# USBStereoAudioCodec.net
KiCad netlist of a schematic drawn in Altium Designer
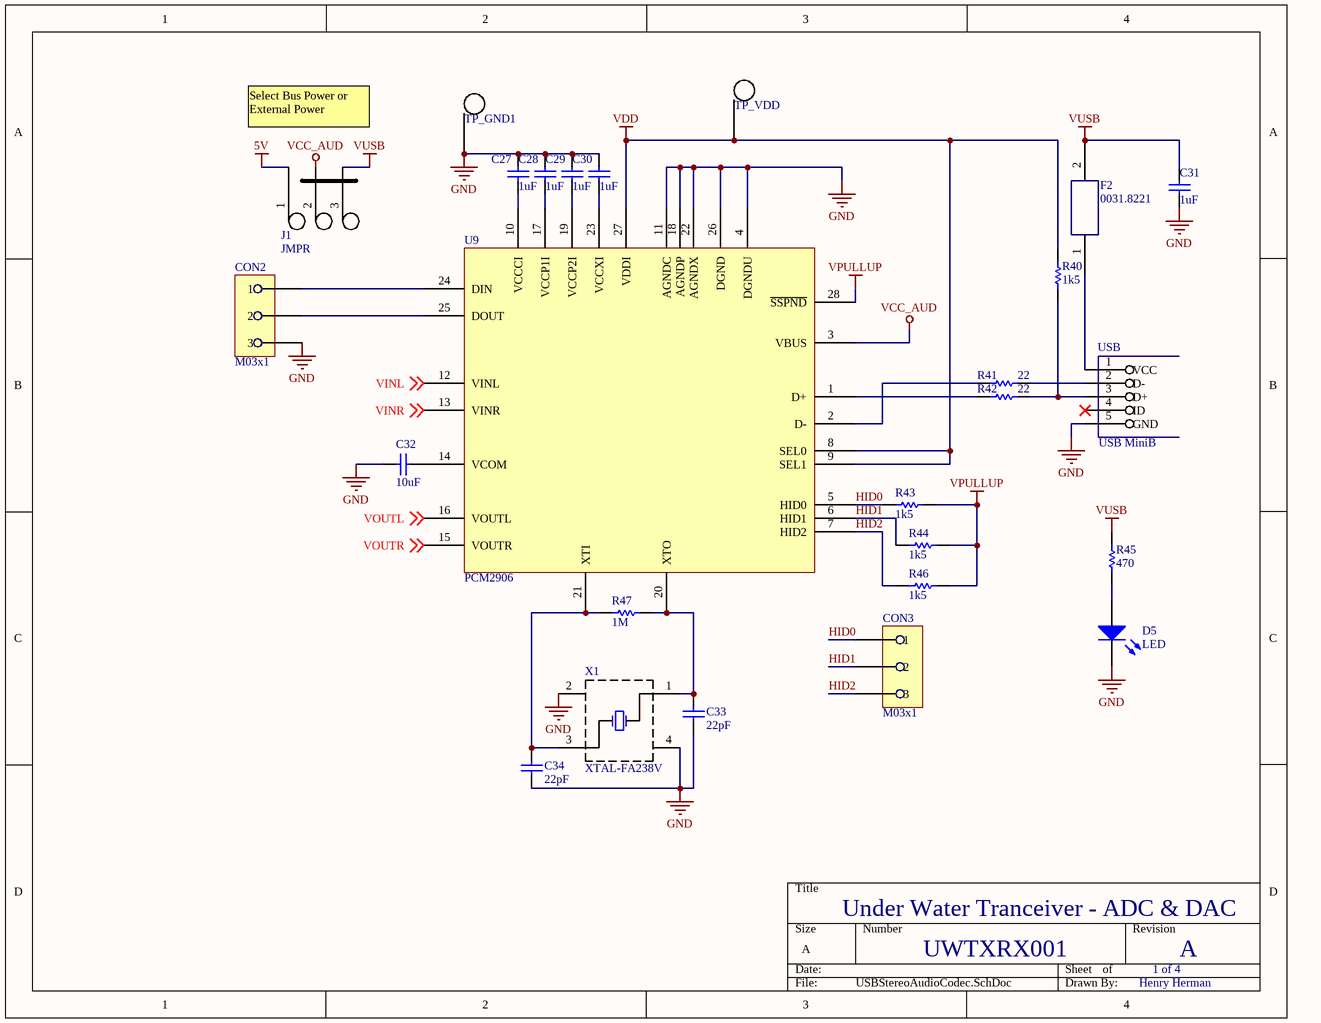
[diagram p0: USBStereoAudioCodec.SchDoc]

(export (version "E")
  (design (tool "Eeschema 10.0.6"))
  (components
    (comp (ref "C27")
      (value "1uF")
      (footprint "SM/C_0805")
      (description "CAP")
      (libsource (lib "Henry1_20_2010") (part "CAP"))
    )
    (comp (ref "C28")
      (value "1uF")
      (footprint "SM/C_0805")
      (description "CAP")
      (libsource (lib "Henry1_20_2010") (part "CAP"))
    )
    (comp (ref "C29")
      (value "1uF")
      (footprint "SM/C_0805")
      (description "CAP")
      (libsource (lib "Henry1_20_2010") (part "CAP"))
    )
    (comp (ref "C30")
      (value "1uF")
      (footprint "SM/C_0805")
      (description "CAP")
      (libsource (lib "Henry1_20_2010") (part "CAP"))
    )
    (comp (ref "C31")
      (value "1uF")
      (footprint "SM/C_0805")
      (description "CAP")
      (libsource (lib "Henry1_20_2010") (part "CAP"))
    )
    (comp (ref "C32")
      (value "10uF")
      (footprint "SM/C_0805")
      (description "CAP")
      (libsource (lib "Henry1_20_2010") (part "CAP"))
    )
    (comp (ref "C33")
      (value "22pF")
      (footprint "SM/C_0805")
      (description "CAP")
      (libsource (lib "Henry1_20_2010") (part "CAP"))
    )
    (comp (ref "C34")
      (value "22pF")
      (footprint "SM/C_0805")
      (description "CAP")
      (libsource (lib "Henry1_20_2010") (part "CAP"))
    )
    (comp (ref "CON2") (value "M03x1") (footprint "M03x1") (libsource (lib "") (part "M03x1_1")))
    (comp (ref "CON3") (value "M03x1") (footprint "M03x1") (libsource (lib "Henry1_20_2010") (part "M03x1")))
    (comp (ref "D5") (value "LED") (footprint "LED-0805") (libsource (lib "Henry1_20_2010") (part "LED")))
    (comp (ref "F2")
      (value "0031.8221")
      (footprint "SM/R_0805")
      (description "Ferrite Bead")
      (fields (field (name "PUBLISHER") "Altium Limited"))
      (libsource (lib "Henry1_20_2010") (part "Ferrite Bead"))
    )
    (comp (ref "J1")
      (value "JMPR")
      (footprint "M03x1-nolock")
      (description "Jumper")
      (fields (field (name "PUBLISHER") "Altium Limited"))
      (libsource (lib "Henry1_20_2010") (part "JMPR-3"))
    )
    (comp (ref "R40")
      (value "1k5")
      (footprint "SM/R_0805")
      (description "Resistor")
      (fields (field (name "Comment") "Res") (field (name "PUBLISHER") "Altium Limited"))
      (libsource (lib "Henry1_20_2010") (part "Res"))
    )
    (comp (ref "R41")
      (value "22")
      (footprint "SM/R_0805")
      (description "Resistor")
      (fields (field (name "Comment") "Res") (field (name "PUBLISHER") "Altium Limited"))
      (libsource (lib "Henry1_20_2010") (part "Res"))
    )
    (comp (ref "R42")
      (value "22")
      (footprint "SM/R_0805")
      (description "Resistor")
      (fields (field (name "Comment") "Res") (field (name "PUBLISHER") "Altium Limited"))
      (libsource (lib "Henry1_20_2010") (part "Res"))
    )
    (comp (ref "R43")
      (value "1k5")
      (footprint "SM/R_0805")
      (description "Resistor")
      (fields (field (name "Comment") "Res") (field (name "PUBLISHER") "Altium Limited"))
      (libsource (lib "Henry1_20_2010") (part "Res"))
    )
    (comp (ref "R44")
      (value "1k5")
      (footprint "SM/R_0805")
      (description "Resistor")
      (fields (field (name "Comment") "Res") (field (name "PUBLISHER") "Altium Limited"))
      (libsource (lib "Henry1_20_2010") (part "Res"))
    )
    (comp (ref "R45")
      (value "470")
      (footprint "SM/R_0805")
      (description "Resistor")
      (fields (field (name "Comment") "Res") (field (name "PUBLISHER") "Altium Limited"))
      (libsource (lib "Henry1_20_2010") (part "Res"))
    )
    (comp (ref "R46")
      (value "1k5")
      (footprint "SM/R_0805")
      (description "Resistor")
      (fields (field (name "Comment") "Res") (field (name "PUBLISHER") "Altium Limited"))
      (libsource (lib "Henry1_20_2010") (part "Res"))
    )
    (comp (ref "R47")
      (value "1M")
      (footprint "SM/R_0805")
      (description "Resistor")
      (fields (field (name "Comment") "Res") (field (name "PUBLISHER") "Altium Limited"))
      (libsource (lib "Henry1_20_2010") (part "Res"))
    )
    (comp (ref "TP_GND1")
      (value "TEST_PT")
      (footprint "TEST_PT_SMD")
      (libsource (lib "Henry1_20_2010") (part "TEST_PT"))
    )
    (comp (ref "TP_VDD")
      (value "TEST_PT")
      (footprint "TEST_PT_SMD")
      (libsource (lib "Henry1_20_2010") (part "TEST_PT"))
    )
    (comp (ref "U9")
      (value "PCM2906")
      (footprint "SSOP-28PIN-TI")
      (libsource (lib "Henry1_20_2010") (part "PCM2906C"))
    )
    (comp (ref "USB")
      (value "USB MiniB")
      (footprint "USB-MINIB")
      (description "NPN General Purpose Amplifier")
      (fields (field (name "PUBLISHER") "Altium Limited"))
      (libsource (lib "Henry1_20_2010") (part "USB MiniB"))
    )
    (comp (ref "X1")
      (value "XTAL-FA238V")
      (footprint "XTAL 12MHz SMD")
      (libsource (lib "Henry1_20_2010") (part "XTAL-FA238V"))
    )
  )
  (nets
    (net (code "1") (name "/HID0") (class "Default")
      (node (ref "CON3") (pin "1") (pinfunction "1_1") (pintype "passive"))
      (node (ref "R43") (pin "1") (pinfunction "1_1") (pintype "passive"))
      (node (ref "U9") (pin "5") (pinfunction "HID0_5") (pintype "passive"))
    )
    (net (code "2") (name "/HID1") (class "Default")
      (node (ref "CON3") (pin "2") (pinfunction "2_2") (pintype "passive"))
      (node (ref "R44") (pin "1") (pinfunction "1_1") (pintype "passive"))
      (node (ref "U9") (pin "6") (pinfunction "HID1_6") (pintype "passive"))
    )
    (net (code "3") (name "/HID2") (class "Default")
      (node (ref "CON3") (pin "3") (pinfunction "3_3") (pintype "passive"))
      (node (ref "R46") (pin "1") (pinfunction "1_1") (pintype "passive"))
      (node (ref "U9") (pin "7") (pinfunction "HID2_7") (pintype "passive"))
    )
    (net (code "4") (name "5V") (class "Default")
      (node (ref "J1") (pin "1") (pinfunction "P1_1") (pintype "power_in"))
    )
    (net (code "5") (name "GND") (class "Default")
      (node (ref "C27") (pin "1") (pinfunction "1_1") (pintype "passive"))
      (node (ref "C28") (pin "1") (pinfunction "1_1") (pintype "passive"))
      (node (ref "C29") (pin "1") (pinfunction "1_1") (pintype "passive"))
      (node (ref "C30") (pin "1") (pinfunction "1_1") (pintype "passive"))
      (node (ref "C31") (pin "2") (pinfunction "2_2") (pintype "passive"))
      (node (ref "C32") (pin "2") (pinfunction "2_2") (pintype "passive"))
      (node (ref "C33") (pin "1") (pinfunction "1_1") (pintype "passive"))
      (node (ref "C34") (pin "1") (pinfunction "1_1") (pintype "passive"))
      (node (ref "CON2") (pin "3") (pinfunction "3_3") (pintype "passive"))
      (node (ref "D5") (pin "2") (pinfunction "K_2") (pintype "passive"))
      (node (ref "TP_GND1") (pin "1") (pinfunction "TP?_1") (pintype "passive"))
      (node (ref "U9") (pin "11") (pinfunction "AGNDC_11") (pintype "passive"))
      (node (ref "U9") (pin "18") (pinfunction "AGNDP_18") (pintype "passive"))
      (node (ref "U9") (pin "22") (pinfunction "AGNDX_22") (pintype "passive"))
      (node (ref "U9") (pin "26") (pinfunction "DGND_26") (pintype "passive"))
      (node (ref "U9") (pin "4") (pinfunction "DGNDU_4") (pintype "passive"))
      (node (ref "USB") (pin "5") (pinfunction "GND_5") (pintype "power_in"))
      (node (ref "X1") (pin "2") (pinfunction "2_2") (pintype "passive"))
      (node (ref "X1") (pin "4") (pinfunction "4_4") (pintype "passive"))
    )
    (net (code "6") (name "Net-(D5-A)") (class "Default")
      (node (ref "D5") (pin "1") (pinfunction "A_1") (pintype "passive"))
      (node (ref "R45") (pin "2") (pinfunction "2_2") (pintype "passive"))
    )
    (net (code "7") (name "Net-(U9-D+)") (class "Default")
      (node (ref "R42") (pin "1") (pinfunction "1_1") (pintype "passive"))
      (node (ref "U9") (pin "1") (pinfunction "D+_1") (pintype "passive"))
    )
    (net (code "8") (name "Net-(U9-D-)") (class "Default")
      (node (ref "R41") (pin "1") (pinfunction "1_1") (pintype "passive"))
      (node (ref "U9") (pin "2") (pinfunction "D-_2") (pintype "passive"))
    )
    (net (code "9") (name "Net-(U9-DIN)") (class "Default")
      (node (ref "CON2") (pin "1") (pinfunction "1_1") (pintype "passive"))
      (node (ref "U9") (pin "24") (pinfunction "DIN_24") (pintype "passive"))
    )
    (net (code "10") (name "Net-(U9-DOUT)") (class "Default")
      (node (ref "CON2") (pin "2") (pinfunction "2_2") (pintype "passive"))
      (node (ref "U9") (pin "25") (pinfunction "DOUT_25") (pintype "passive"))
    )
    (net (code "11") (name "Net-(U9-VCCCI)") (class "Default")
      (node (ref "C27") (pin "2") (pinfunction "2_2") (pintype "passive"))
      (node (ref "U9") (pin "10") (pinfunction "VCCCI_10") (pintype "passive"))
    )
    (net (code "12") (name "Net-(U9-VCCP1I)") (class "Default")
      (node (ref "C28") (pin "2") (pinfunction "2_2") (pintype "passive"))
      (node (ref "U9") (pin "17") (pinfunction "VCCP1I_17") (pintype "passive"))
    )
    (net (code "13") (name "Net-(U9-VCCP2I)") (class "Default")
      (node (ref "C29") (pin "2") (pinfunction "2_2") (pintype "passive"))
      (node (ref "U9") (pin "19") (pinfunction "VCCP2I_19") (pintype "passive"))
    )
    (net (code "14") (name "Net-(U9-VCCXI)") (class "Default")
      (node (ref "C30") (pin "2") (pinfunction "2_2") (pintype "passive"))
      (node (ref "U9") (pin "23") (pinfunction "VCCXI_23") (pintype "passive"))
    )
    (net (code "15") (name "Net-(U9-VCOM)") (class "Default")
      (node (ref "C32") (pin "1") (pinfunction "1_1") (pintype "passive"))
      (node (ref "U9") (pin "14") (pinfunction "VCOM_14") (pintype "passive"))
    )
    (net (code "16") (name "Net-(U9-XTI)") (class "Default")
      (node (ref "C34") (pin "2") (pinfunction "2_2") (pintype "passive"))
      (node (ref "R47") (pin "2") (pinfunction "2_2") (pintype "passive"))
      (node (ref "U9") (pin "21") (pinfunction "XTI_21") (pintype "passive"))
      (node (ref "X1") (pin "3") (pinfunction "3_3") (pintype "passive"))
    )
    (net (code "17") (name "Net-(U9-XTO)") (class "Default")
      (node (ref "C33") (pin "2") (pinfunction "2_2") (pintype "passive"))
      (node (ref "R47") (pin "1") (pinfunction "1_1") (pintype "passive"))
      (node (ref "U9") (pin "20") (pinfunction "XTO_20") (pintype "passive"))
      (node (ref "X1") (pin "1") (pinfunction "1_1") (pintype "passive"))
    )
    (net (code "18") (name "Net-(USB-D+)") (class "Default")
      (node (ref "R40") (pin "2") (pinfunction "2_2") (pintype "passive"))
      (node (ref "R42") (pin "2") (pinfunction "2_2") (pintype "passive"))
      (node (ref "USB") (pin "3") (pinfunction "D+_3") (pintype "power_in"))
    )
    (net (code "19") (name "Net-(USB-D-)") (class "Default")
      (node (ref "R41") (pin "2") (pinfunction "2_2") (pintype "passive"))
      (node (ref "USB") (pin "2") (pinfunction "D-_2") (pintype "power_in"))
    )
    (net (code "20") (name "Net-(USB-VCC)") (class "Default")
      (node (ref "F2") (pin "1") (pintype "power_in"))
      (node (ref "USB") (pin "1") (pinfunction "VCC_1") (pintype "power_in"))
    )
    (net (code "21") (name "VCC_AUD") (class "Default")
      (node (ref "J1") (pin "2") (pinfunction "P2_2") (pintype "power_in"))
      (node (ref "U9") (pin "3") (pinfunction "VBUS_3") (pintype "passive"))
    )
    (net (code "22") (name "VDD") (class "Default")
      (node (ref "R40") (pin "1") (pinfunction "1_1") (pintype "passive"))
      (node (ref "TP_VDD") (pin "1") (pinfunction "TP?_1") (pintype "passive"))
      (node (ref "U9") (pin "27") (pinfunction "VDDI_27") (pintype "passive"))
      (node (ref "U9") (pin "8") (pinfunction "SEL0_8") (pintype "passive"))
      (node (ref "U9") (pin "9") (pinfunction "SEL1_9") (pintype "passive"))
    )
    (net (code "23") (name "VINL") (class "Default")
      (node (ref "U9") (pin "12") (pinfunction "VINL_12") (pintype "passive"))
    )
    (net (code "24") (name "VINR") (class "Default")
      (node (ref "U9") (pin "13") (pinfunction "VINR_13") (pintype "passive"))
    )
    (net (code "25") (name "VOUTL") (class "Default")
      (node (ref "U9") (pin "16") (pinfunction "VOUTL_16") (pintype "passive"))
    )
    (net (code "26") (name "VOUTR") (class "Default")
      (node (ref "U9") (pin "15") (pinfunction "VOUTR_15") (pintype "passive"))
    )
    (net (code "27") (name "VPULLUP") (class "Default")
      (node (ref "R43") (pin "2") (pinfunction "2_2") (pintype "passive"))
      (node (ref "R44") (pin "2") (pinfunction "2_2") (pintype "passive"))
      (node (ref "R46") (pin "2") (pinfunction "2_2") (pintype "passive"))
      (node (ref "U9") (pin "28") (pinfunction "~{SSPND}_28") (pintype "passive"))
    )
    (net (code "28") (name "VUSB") (class "Default")
      (node (ref "C31") (pin "1") (pinfunction "1_1") (pintype "passive"))
      (node (ref "F2") (pin "2") (pintype "power_in"))
      (node (ref "J1") (pin "3") (pinfunction "3_3") (pintype "power_in"))
      (node (ref "R45") (pin "1") (pinfunction "1_1") (pintype "passive"))
    )
    (net (code "29") (name "unconnected-(USB-ID-Pad4)") (class "Default")
      (node (ref "USB") (pin "4") (pinfunction "ID_4") (pintype "power_in+no_connect"))
    )
  )
)
